# 03_-_MCU_and_Conn.net
KiCad netlist of a schematic drawn in Altium Designer
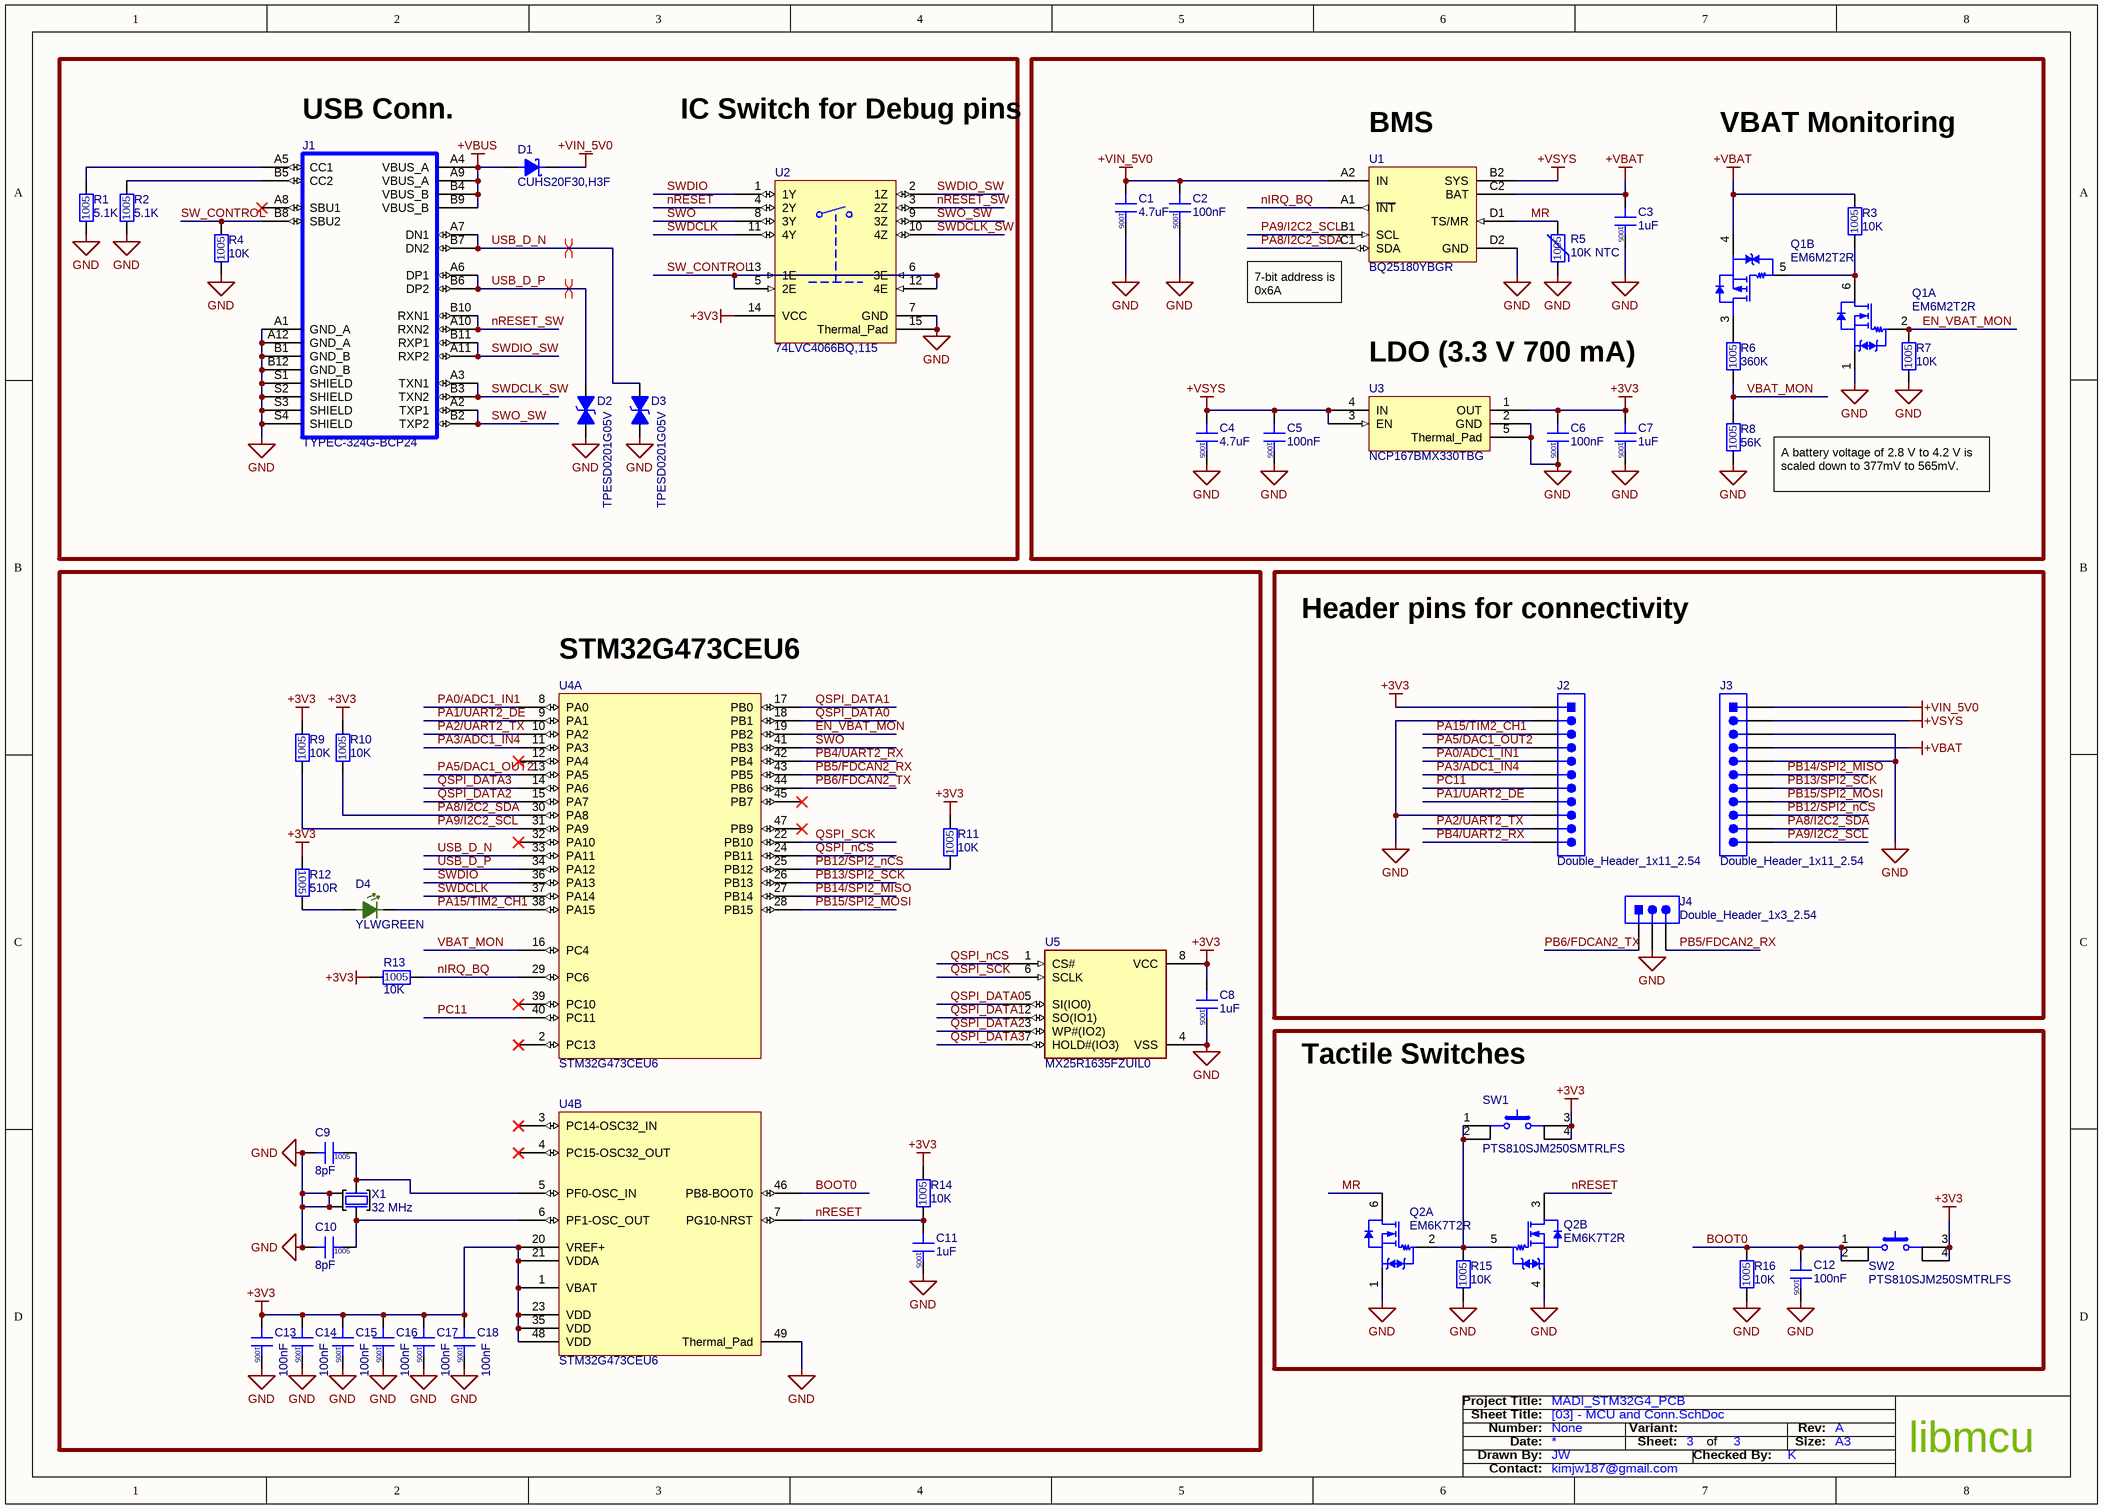
[diagram p0: [03] - MCU and Conn.SchDoc]

(export (version "E")
  (design (tool "Eeschema 10.0.6"))
  (components
    (comp (ref "C1")
      (value "4.7uF")
      (footprint "CAPC1005X06N")
      (description "CAP CER 4.7UF 10V X5R 0402")
      (fields
        (field (name "MANUFACTURER") "Samsung")
        (field (name "MANUFACTURER PART NUMBER") "CL05A475MP5NRNC")
      )
      (libsource (lib "Schlib-master") (part "CL05A475MP5NRNC"))
    )
    (comp (ref "C2")
      (value "100nF")
      (footprint "CAPC1005X06N")
      (description "CAP CER 0.1UF 50V X7R 0402")
      (fields
        (field (name "MANUFACTURER") "Murata")
        (field (name "MANUFACTURER PART NUMBER") "GRM155R71H104KE14D")
      )
      (libsource (lib "Schlib-master") (part "GRM155R71H104KE14D"))
    )
    (comp (ref "C3")
      (value "1uF")
      (footprint "CAPC1005X06N")
      (description "CAP CER 1UF 16V X5R 0402")
      (fields
        (field (name "MANUFACTURER") "Samsung")
        (field (name "MANUFACTURER PART NUMBER") "CL05A105KO5NNNC")
      )
      (libsource (lib "Schlib-master") (part "CL05A105KO5NNNC"))
    )
    (comp (ref "C4")
      (value "4.7uF")
      (footprint "CAPC1005X06N")
      (description "CAP CER 4.7UF 10V X5R 0402")
      (fields
        (field (name "MANUFACTURER") "Samsung")
        (field (name "MANUFACTURER PART NUMBER") "CL05A475MP5NRNC")
      )
      (libsource (lib "Schlib-master") (part "CL05A475MP5NRNC"))
    )
    (comp (ref "C5")
      (value "100nF")
      (footprint "CAPC1005X06N")
      (description "CAP CER 0.1UF 50V X7R 0402")
      (fields
        (field (name "MANUFACTURER") "Murata")
        (field (name "MANUFACTURER PART NUMBER") "GRM155R71H104KE14D")
      )
      (libsource (lib "Schlib-master") (part "GRM155R71H104KE14D"))
    )
    (comp (ref "C6")
      (value "100nF")
      (footprint "CAPC1005X06N")
      (description "CAP CER 0.1UF 50V X7R 0402")
      (fields
        (field (name "MANUFACTURER") "Murata")
        (field (name "MANUFACTURER PART NUMBER") "GRM155R71H104KE14D")
      )
      (libsource (lib "Schlib-master") (part "GRM155R71H104KE14D"))
    )
    (comp (ref "C7")
      (value "1uF")
      (footprint "CAPC1005X06N")
      (description "CAP CER 1UF 16V X5R 0402")
      (fields
        (field (name "MANUFACTURER") "Samsung")
        (field (name "MANUFACTURER PART NUMBER") "CL05A105KO5NNNC")
      )
      (libsource (lib "Schlib-master") (part "CL05A105KO5NNNC"))
    )
    (comp (ref "C8")
      (value "1uF")
      (footprint "CAPC1005X06N")
      (description "CAP CER 1UF 16V X5R 0402")
      (fields
        (field (name "MANUFACTURER") "Samsung")
        (field (name "MANUFACTURER PART NUMBER") "CL05A105KO5NNNC")
      )
      (libsource (lib "Schlib-master") (part "CL05A105KO5NNNC"))
    )
    (comp (ref "C9")
      (value "8pF")
      (footprint "CAPC1005X06N")
      (description "CAP CER 8PF 50V C0G/NP0 0402")
      (fields
        (field (name "MANUFACTURER") "Murata")
        (field (name "MANUFACTURER PART NUMBER") "GRM1555C1H8R0DA01D")
      )
      (libsource (lib "Schlib-master") (part "GRM1555C1H8R0DA01D"))
    )
    (comp (ref "C10")
      (value "8pF")
      (footprint "CAPC1005X06N")
      (description "CAP CER 8PF 50V C0G/NP0 0402")
      (fields
        (field (name "MANUFACTURER") "Murata")
        (field (name "MANUFACTURER PART NUMBER") "GRM1555C1H8R0DA01D")
      )
      (libsource (lib "Schlib-master") (part "GRM1555C1H8R0DA01D"))
    )
    (comp (ref "C11")
      (value "1uF")
      (footprint "CAPC1005X06N")
      (description "CAP CER 1UF 16V X5R 0402")
      (fields
        (field (name "MANUFACTURER") "Samsung")
        (field (name "MANUFACTURER PART NUMBER") "CL05A105KO5NNNC")
      )
      (libsource (lib "Schlib-master") (part "CL05A105KO5NNNC"))
    )
    (comp (ref "C12")
      (value "100nF")
      (footprint "CAPC1005X06N")
      (description "CAP CER 0.1UF 50V X7R 0402")
      (fields
        (field (name "MANUFACTURER") "Murata")
        (field (name "MANUFACTURER PART NUMBER") "GRM155R71H104KE14D")
      )
      (libsource (lib "Schlib-master") (part "GRM155R71H104KE14D"))
    )
    (comp (ref "C13")
      (value "100nF")
      (footprint "CAPC1005X06N")
      (description "CAP CER 0.1UF 50V X7R 0402")
      (fields
        (field (name "MANUFACTURER") "Murata")
        (field (name "MANUFACTURER PART NUMBER") "GRM155R71H104KE14D")
      )
      (libsource (lib "Schlib-master") (part "GRM155R71H104KE14D"))
    )
    (comp (ref "C14")
      (value "100nF")
      (footprint "CAPC1005X06N")
      (description "CAP CER 0.1UF 50V X7R 0402")
      (fields
        (field (name "MANUFACTURER") "Murata")
        (field (name "MANUFACTURER PART NUMBER") "GRM155R71H104KE14D")
      )
      (libsource (lib "Schlib-master") (part "GRM155R71H104KE14D"))
    )
    (comp (ref "C15")
      (value "100nF")
      (footprint "CAPC1005X06N")
      (description "CAP CER 0.1UF 50V X7R 0402")
      (fields
        (field (name "MANUFACTURER") "Murata")
        (field (name "MANUFACTURER PART NUMBER") "GRM155R71H104KE14D")
      )
      (libsource (lib "Schlib-master") (part "GRM155R71H104KE14D"))
    )
    (comp (ref "C16")
      (value "100nF")
      (footprint "CAPC1005X06N")
      (description "CAP CER 0.1UF 50V X7R 0402")
      (fields
        (field (name "MANUFACTURER") "Murata")
        (field (name "MANUFACTURER PART NUMBER") "GRM155R71H104KE14D")
      )
      (libsource (lib "Schlib-master") (part "GRM155R71H104KE14D"))
    )
    (comp (ref "C17")
      (value "100nF")
      (footprint "CAPC1005X06N")
      (description "CAP CER 0.1UF 50V X7R 0402")
      (fields
        (field (name "MANUFACTURER") "Murata")
        (field (name "MANUFACTURER PART NUMBER") "GRM155R71H104KE14D")
      )
      (libsource (lib "Schlib-master") (part "GRM155R71H104KE14D"))
    )
    (comp (ref "C18")
      (value "100nF")
      (footprint "CAPC1005X06N")
      (description "CAP CER 0.1UF 50V X7R 0402")
      (fields
        (field (name "MANUFACTURER") "Murata")
        (field (name "MANUFACTURER PART NUMBER") "GRM155R71H104KE14D")
      )
      (libsource (lib "Schlib-master") (part "GRM155R71H104KE14D"))
    )
    (comp (ref "D1")
      (value "CUHS20F30,H3F")
      (footprint "US2H-DIODE")
      (description "DIODE SCHOTTKY 30V 2A US2H")
      (fields (field (name "MANUFACTURER") "Toshiba"))
      (libsource (lib "Schlib-master") (part "CUHS20F30,H3F"))
    )
    (comp (ref "D2")
      (value "TPESD0201G05V")
      (footprint "DIOC0603X03N")
      (description "TVS DIODE 5.5VWM 40VC 0201")
      (fields (field (name "MANUFACTURER") "TECH PUBLIC"))
      (libsource (lib "Schlib-master") (part "TPESD0201G05V"))
    )
    (comp (ref "D3")
      (value "TPESD0201G05V")
      (footprint "DIOC0603X03N")
      (description "TVS DIODE 5.5VWM 40VC 0201")
      (fields (field (name "MANUFACTURER") "TECH PUBLIC"))
      (libsource (lib "Schlib-master") (part "TPESD0201G05V"))
    )
    (comp (ref "D4")
      (value "YLWGREEN")
      (footprint "LDIOC1608X08N")
      (description "LED YLW/GREEN DIFFUSED 1608 SMD")
      (fields
        (field (name "MANUFACTURER") "Everlight")
        (field (name "MANUFACTURER PART NUMBER") "19-217/G7C-AN1P2/3T")
      )
      (libsource (lib "Schlib-master") (part "19-217/G7C-AN1P2/3T"))
    )
    (comp (ref "J1")
      (value "TYPEC-324G-BCP24")
      (footprint "KUSBX-SMT3-CS-BTR_KYC")
      (description "CONN RCPT USB TYPE C, SMT PINS, TH SHIELD")
      (fields (field (name "MANUFACTURER") "XUNPU"))
      (libsource (lib "Schlib-master") (part "TYPEC-324G-BCP24"))
    )
    (comp (ref "J2")
      (value "Double_Header_1x11_2.54")
      (footprint "1x11_DOUBLE_HEADER_2.54")
      (libsource (lib "Schlib-master") (part "Double_Header_1x11_2.54"))
    )
    (comp (ref "J3")
      (value "Double_Header_1x11_2.54")
      (footprint "1x11_DOUBLE_HEADER_2.54")
      (libsource (lib "") (part "Double_Header_1x11_2.54_1"))
    )
    (comp (ref "J4")
      (value "Double_Header_1x3_2.54")
      (footprint "1x3_DOUBLE_HEADER_2.54")
      (libsource (lib "Schlib-master") (part "Double_Header_1x3_2.54"))
    )
    (comp (ref "Q1")
      (value "EM6M2T2R")
      (footprint "SOTFL50P160X55-6N")
      (description "MOSFET N/P-CH 20V 0.2A EMT6")
      (fields (field (name "MANUFACTURER") "Rohm"))
      (libsource (lib "Schlib-master") (part "EM6M2T2R"))
    )
    (comp (ref "Q2")
      (value "EM6K7T2R")
      (footprint "SOTFL50P160X55-6N")
      (description "MOSFET 2N-CH 20V 0.2A EMT6")
      (fields (field (name "MANUFACTURER") "Rohm"))
      (libsource (lib "Schlib-master") (part "EM6K7T2R"))
    )
    (comp (ref "R1")
      (value "5.1K")
      (footprint "RESC1005X04N")
      (description "RES SMD 5.1K OHM 1% 1/16W 0402")
      (fields
        (field (name "MANUFACTURER") "Yageo")
        (field (name "MANUFACTURER PART NUMBER") "RC0402FR-075K1L")
      )
      (libsource (lib "Schlib-master") (part "RC0402FR-075K1L"))
    )
    (comp (ref "R2")
      (value "5.1K")
      (footprint "RESC1005X04N")
      (description "RES SMD 5.1K OHM 1% 1/16W 0402")
      (fields
        (field (name "MANUFACTURER") "Yageo")
        (field (name "MANUFACTURER PART NUMBER") "RC0402FR-075K1L")
      )
      (libsource (lib "Schlib-master") (part "RC0402FR-075K1L"))
    )
    (comp (ref "R3")
      (value "10K")
      (footprint "RESC1005X04N")
      (description "RES SMD 10K OHM 1% 1/16W 0402")
      (fields
        (field (name "MANUFACTURER") "Yageo")
        (field (name "MANUFACTURER PART NUMBER") "RC0402FR-0710KL")
      )
      (libsource (lib "Schlib-master") (part "RC0402FR-0710KL"))
    )
    (comp (ref "R4")
      (value "10K")
      (footprint "RESC1005X04N")
      (description "RES SMD 10K OHM 1% 1/16W 0402")
      (fields
        (field (name "MANUFACTURER") "Yageo")
        (field (name "MANUFACTURER PART NUMBER") "RC0402FR-0710KL")
      )
      (libsource (lib "Schlib-master") (part "RC0402FR-0710KL"))
    )
    (comp (ref "R5")
      (value "10K NTC")
      (footprint "NTC1005X05N")
      (description "THERMISTOR NTC 10KOHM 3380K 0402")
      (fields
        (field (name "MANUFACTURER") "Murata")
        (field (name "MANUFACTURER PART NUMBER") "NCP15XH103F03RC")
      )
      (libsource (lib "Schlib-master") (part "NCP15XH103F03RC"))
    )
    (comp (ref "R6")
      (value "360K")
      (footprint "RESC1005X04N")
      (description "RES SMD 360K OHM 1% 1/16W 0402")
      (fields
        (field (name "MANUFACTURER") "Yageo")
        (field (name "MANUFACTURER PART NUMBER") "RC0402FR-07360KL")
      )
      (libsource (lib "Schlib-master") (part "RC0402FR-07360KL"))
    )
    (comp (ref "R7")
      (value "10K")
      (footprint "RESC1005X04N")
      (description "RES SMD 10K OHM 1% 1/16W 0402")
      (fields
        (field (name "MANUFACTURER") "Yageo")
        (field (name "MANUFACTURER PART NUMBER") "RC0402FR-0710KL")
      )
      (libsource (lib "Schlib-master") (part "RC0402FR-0710KL"))
    )
    (comp (ref "R8")
      (value "56K")
      (footprint "RESC1005X04N")
      (description "RES SMD 56K OHM 1% 1/16W 0402")
      (fields
        (field (name "MANUFACTURER") "Yageo")
        (field (name "MANUFACTURER PART NUMBER") "RC0402FR-0756KL")
      )
      (libsource (lib "Schlib-master") (part "RC0402FR-0756KL"))
    )
    (comp (ref "R9")
      (value "10K")
      (footprint "RESC1005X04N")
      (description "RES SMD 10K OHM 1% 1/16W 0402")
      (fields
        (field (name "MANUFACTURER") "Yageo")
        (field (name "MANUFACTURER PART NUMBER") "RC0402FR-0710KL")
      )
      (libsource (lib "Schlib-master") (part "RC0402FR-0710KL"))
    )
    (comp (ref "R10")
      (value "10K")
      (footprint "RESC1005X04N")
      (description "RES SMD 10K OHM 1% 1/16W 0402")
      (fields
        (field (name "MANUFACTURER") "Yageo")
        (field (name "MANUFACTURER PART NUMBER") "RC0402FR-0710KL")
      )
      (libsource (lib "Schlib-master") (part "RC0402FR-0710KL"))
    )
    (comp (ref "R11")
      (value "10K")
      (footprint "RESC1005X04N")
      (description "RES SMD 10K OHM 1% 1/16W 0402")
      (fields
        (field (name "MANUFACTURER") "Yageo")
        (field (name "MANUFACTURER PART NUMBER") "RC0402FR-0710KL")
      )
      (libsource (lib "Schlib-master") (part "RC0402FR-0710KL"))
    )
    (comp (ref "R12")
      (value "510R")
      (footprint "RESC1005X04N")
      (description "RES SMD 510 OHM 1% 1/16W 0402")
      (fields (field (name "TOLERANCE") "1%") (field (name "MANUFACTURER") "Yageo"))
      (libsource (lib "Schlib-master") (part "RC0402FR-07510RL"))
    )
    (comp (ref "R13")
      (value "10K")
      (footprint "RESC1005X04N")
      (description "RES SMD 10K OHM 1% 1/16W 0402")
      (fields
        (field (name "MANUFACTURER") "Yageo")
        (field (name "MANUFACTURER PART NUMBER") "RC0402FR-0710KL")
      )
      (libsource (lib "") (part "RC0402FR-0710KL_1"))
    )
    (comp (ref "R14")
      (value "10K")
      (footprint "RESC1005X04N")
      (description "RES SMD 10K OHM 1% 1/16W 0402")
      (fields
        (field (name "MANUFACTURER") "Yageo")
        (field (name "MANUFACTURER PART NUMBER") "RC0402FR-0710KL")
      )
      (libsource (lib "Schlib-master") (part "RC0402FR-0710KL"))
    )
    (comp (ref "R15")
      (value "10K")
      (footprint "RESC1005X04N")
      (description "RES SMD 10K OHM 1% 1/16W 0402")
      (fields
        (field (name "MANUFACTURER") "Yageo")
        (field (name "MANUFACTURER PART NUMBER") "RC0402FR-0710KL")
      )
      (libsource (lib "Schlib-master") (part "RC0402FR-0710KL"))
    )
    (comp (ref "R16")
      (value "10K")
      (footprint "RESC1005X04N")
      (description "RES SMD 10K OHM 1% 1/16W 0402")
      (fields
        (field (name "MANUFACTURER") "Yageo")
        (field (name "MANUFACTURER PART NUMBER") "RC0402FR-0710KL")
      )
      (libsource (lib "Schlib-master") (part "RC0402FR-0710KL"))
    )
    (comp (ref "SW1")
      (value "PTS810SJM250SMTRLFS")
      (footprint "PTS810")
      (description "SWITCH TACTILE SPST-NO 0.05A 16V")
      (fields (field (name "MANUFACTURER") "ITT C&K"))
      (libsource (lib "Schlib-master") (part "PTS810SJM250SMTRLFS"))
    )
    (comp (ref "SW2")
      (value "PTS810SJM250SMTRLFS")
      (footprint "PTS810")
      (description "SWITCH TACTILE SPST-NO 0.05A 16V")
      (fields (field (name "MANUFACTURER") "ITT C&K"))
      (libsource (lib "Schlib-master") (part "PTS810SJM250SMTRLFS"))
    )
    (comp (ref "U1")
      (value "BQ25180YBGR")
      (footprint "BGA8C40P2X4_100X155X50_YBG0008")
      (description "IC 1-A LI-ION IC PROGRAMMABLE CHARG")
      (fields (field (name "MANUFACTURER") "Texas Instruments"))
      (libsource (lib "Schlib-master") (part "BQ25180YBGR"))
    )
    (comp (ref "U2")
      (value "74LVC4066BQ,115")
      (footprint "QFN50P250X300X100_HS-15N")
      (description "IC SWITCH QUAD SPST 14DHVQFN")
      (fields (field (name "MANUFACTURER") "Nexperia"))
      (libsource (lib "Schlib-master") (part "74LVC4066BQ,115"))
    )
    (comp (ref "U3")
      (value "NCP167BMX330TBG")
      (footprint "NCP167")
      (description "IC REG LINEAR 3.3V 700MA 4XDFN")
      (fields (field (name "MANUFACTURER") "ON Semiconductor"))
      (libsource (lib "Schlib-master") (part "NCP167BMX330TBG"))
    )
    (comp (ref "U4")
      (value "STM32G473CEU6")
      (footprint "QFN50P700X700X60_HS-49N")
      (description "IC MCU 32BIT 512KB FLSH 48UFQFPN")
      (fields (field (name "MANUFACTURER") "STMicroelectronics"))
      (libsource (lib "Schlib-master") (part "STM32G473CEU6"))
    )
    (comp (ref "U5")
      (value "MX25R1635FZUIL0")
      (footprint "USON8_3X2")
      (description "IC FLASH 16MBIT SPI/QUAD 8USON")
      (fields (field (name "MANUFACTURER") "Macronix"))
      (libsource (lib "Schlib-master") (part "MX25R1635FZUIL0"))
    )
    (comp (ref "X1")
      (value "32 MHz")
      (footprint "XT2016_ECS")
      (description "CRYSTAL 32.0000MHZ 8PF SMD")
      (fields
        (field (name "MANUFACTURER") "Seiko")
        (field (name "MANUFACTURER PART NUMBER") "Q22FA1280002500")
      )
      (libsource (lib "Schlib-master") (part "Q22FA1280002500"))
    )
  )
  (nets
    (net (code "1") (name "+3V3") (class "Default")
      (node (ref "C13") (pin "2") (pinfunction "2_2") (pintype "passive"))
      (node (ref "C14") (pin "2") (pinfunction "2_2") (pintype "passive"))
      (node (ref "C15") (pin "2") (pinfunction "2_2") (pintype "passive"))
      (node (ref "C16") (pin "2") (pinfunction "2_2") (pintype "passive"))
      (node (ref "C17") (pin "2") (pinfunction "2_2") (pintype "passive"))
      (node (ref "C18") (pin "2") (pinfunction "2_2") (pintype "passive"))
      (node (ref "C6") (pin "2") (pinfunction "2_2") (pintype "passive"))
      (node (ref "C7") (pin "2") (pinfunction "2_2") (pintype "passive"))
      (node (ref "C8") (pin "2") (pinfunction "2_2") (pintype "passive"))
      (node (ref "J2") (pin "1") (pinfunction "1_1") (pintype "passive"))
      (node (ref "R10") (pin "2") (pinfunction "2_2") (pintype "passive"))
      (node (ref "R11") (pin "2") (pinfunction "2_2") (pintype "passive"))
      (node (ref "R12") (pin "2") (pinfunction "2_2") (pintype "passive"))
      (node (ref "R13") (pin "1") (pinfunction "1_1") (pintype "passive"))
      (node (ref "R14") (pin "2") (pinfunction "2_2") (pintype "passive"))
      (node (ref "R9") (pin "2") (pinfunction "2_2") (pintype "passive"))
      (node (ref "SW1") (pin "3") (pinfunction "2_3") (pintype "passive"))
      (node (ref "SW1") (pin "4") (pinfunction "1_4") (pintype "passive"))
      (node (ref "SW2") (pin "3") (pinfunction "2_3") (pintype "passive"))
      (node (ref "SW2") (pin "4") (pinfunction "1_4") (pintype "passive"))
      (node (ref "U2") (pin "14") (pinfunction "VCC_14") (pintype "power_in"))
      (node (ref "U3") (pin "1") (pinfunction "OUT_1") (pintype "power_in"))
      (node (ref "U4") (pin "1") (pinfunction "VBAT_1") (pintype "power_in"))
      (node (ref "U4") (pin "20") (pinfunction "VREF+_20") (pintype "power_in"))
      (node (ref "U4") (pin "21") (pinfunction "VDDA_21") (pintype "power_in"))
      (node (ref "U4") (pin "23") (pinfunction "VDD_23") (pintype "power_in"))
      (node (ref "U4") (pin "35") (pinfunction "VDD_35") (pintype "power_in"))
      (node (ref "U4") (pin "48") (pinfunction "VDD_48") (pintype "power_in"))
      (node (ref "U5") (pin "8") (pinfunction "VCC_8") (pintype "power_in"))
    )
    (net (code "2") (name "+VBAT") (class "Default")
      (node (ref "C3") (pin "2") (pinfunction "2_2") (pintype "passive"))
      (node (ref "J3") (pin "4") (pinfunction "4_4") (pintype "passive"))
      (node (ref "Q1") (pin "4") (pinfunction "S_4") (pintype "passive"))
      (node (ref "R3") (pin "2") (pinfunction "2_2") (pintype "passive"))
      (node (ref "U1") (pin "C2") (pinfunction "BAT_C2") (pintype "power_in"))
    )
    (net (code "3") (name "+VBUS") (class "Default")
      (node (ref "D1") (pin "2") (pinfunction "Anode_2") (pintype "passive"))
      (node (ref "J1") (pin "A4") (pinfunction "VBUS_A_A4") (pintype "power_in"))
      (node (ref "J1") (pin "A9") (pinfunction "VBUS_A_A9") (pintype "power_in"))
      (node (ref "J1") (pin "B4") (pinfunction "VBUS_B_B4") (pintype "power_in"))
      (node (ref "J1") (pin "B9") (pinfunction "VBUS_B_B9") (pintype "power_in"))
    )
    (net (code "4") (name "+VIN_5V0") (class "Default")
      (node (ref "C1") (pin "2") (pinfunction "2_2") (pintype "passive"))
      (node (ref "C2") (pin "2") (pinfunction "2_2") (pintype "passive"))
      (node (ref "D1") (pin "1") (pinfunction "Cathode_1") (pintype "passive"))
      (node (ref "J3") (pin "1") (pinfunction "1_1") (pintype "passive"))
      (node (ref "U1") (pin "A2") (pinfunction "IN_A2") (pintype "power_in"))
    )
    (net (code "5") (name "+VSYS") (class "Default")
      (node (ref "C4") (pin "2") (pinfunction "2_2") (pintype "passive"))
      (node (ref "C5") (pin "2") (pinfunction "2_2") (pintype "passive"))
      (node (ref "J3") (pin "2") (pinfunction "2_2") (pintype "passive"))
      (node (ref "U1") (pin "B2") (pinfunction "SYS_B2") (pintype "power_in"))
      (node (ref "U3") (pin "3") (pinfunction "EN_3") (pintype "input"))
      (node (ref "U3") (pin "4") (pinfunction "IN_4") (pintype "power_in"))
    )
    (net (code "6") (name "/BOOT0") (class "Default")
      (node (ref "C12") (pin "2") (pinfunction "2_2") (pintype "passive"))
      (node (ref "R16") (pin "2") (pinfunction "2_2") (pintype "passive"))
      (node (ref "SW2") (pin "1") (pinfunction "1_1") (pintype "passive"))
      (node (ref "SW2") (pin "2") (pinfunction "2_2") (pintype "passive"))
      (node (ref "U4") (pin "46") (pinfunction "PB8-BOOT0_46") (pintype "bidirectional"))
    )
    (net (code "7") (name "/EN_VBAT_MON") (class "Default")
      (node (ref "Q1") (pin "2") (pinfunction "G_2") (pintype "passive"))
      (node (ref "R7") (pin "2") (pinfunction "2_2") (pintype "passive"))
      (node (ref "U4") (pin "19") (pinfunction "PB2_19") (pintype "bidirectional"))
    )
    (net (code "8") (name "/MR") (class "Default")
      (node (ref "Q2") (pin "6") (pinfunction "D_6") (pintype "passive"))
      (node (ref "R5") (pin "2") (pinfunction "2_2") (pintype "passive"))
      (node (ref "U1") (pin "D1") (pinfunction "TS/MR_D1") (pintype "input"))
    )
    (net (code "9") (name "/PA0{slash}ADC1_IN1") (class "Default")
      (node (ref "J2") (pin "5") (pinfunction "5_5") (pintype "passive"))
      (node (ref "U4") (pin "8") (pinfunction "PA0_8") (pintype "bidirectional"))
    )
    (net (code "10") (name "/PA1{slash}UART2_DE") (class "Default")
      (node (ref "J2") (pin "8") (pinfunction "8_8") (pintype "passive"))
      (node (ref "U4") (pin "9") (pinfunction "PA1_9") (pintype "bidirectional"))
    )
    (net (code "11") (name "/PA2{slash}UART2_TX") (class "Default")
      (node (ref "J2") (pin "10") (pinfunction "10_10") (pintype "passive"))
      (node (ref "U4") (pin "10") (pinfunction "PA2_10") (pintype "bidirectional"))
    )
    (net (code "12") (name "/PA3{slash}ADC1_IN4") (class "Default")
      (node (ref "J2") (pin "6") (pinfunction "6_6") (pintype "passive"))
      (node (ref "U4") (pin "11") (pinfunction "PA3_11") (pintype "bidirectional"))
    )
    (net (code "13") (name "/PA5{slash}DAC1_OUT2") (class "Default")
      (node (ref "J2") (pin "4") (pinfunction "4_4") (pintype "passive"))
      (node (ref "U4") (pin "13") (pinfunction "PA5_13") (pintype "bidirectional"))
    )
    (net (code "14") (name "/PA8{slash}I2C2_SDA") (class "Default")
      (node (ref "J3") (pin "10") (pinfunction "10_10") (pintype "passive"))
      (node (ref "R10") (pin "1") (pinfunction "1_1") (pintype "passive"))
      (node (ref "U1") (pin "C1") (pinfunction "SDA_C1") (pintype "bidirectional"))
      (node (ref "U4") (pin "30") (pinfunction "PA8_30") (pintype "bidirectional"))
    )
    (net (code "15") (name "/PA9{slash}I2C2_SCL") (class "Default")
      (node (ref "J3") (pin "11") (pinfunction "11_11") (pintype "passive"))
      (node (ref "R9") (pin "1") (pinfunction "1_1") (pintype "passive"))
      (node (ref "U1") (pin "B1") (pinfunction "SCL_B1") (pintype "input"))
      (node (ref "U4") (pin "31") (pinfunction "PA9_31") (pintype "bidirectional"))
    )
    (net (code "16") (name "/PA15{slash}TIM2_CH1") (class "Default")
      (node (ref "D4") (pin "K") (pinfunction "2_K") (pintype "passive"))
      (node (ref "J2") (pin "3") (pinfunction "3_3") (pintype "passive"))
      (node (ref "U4") (pin "38") (pinfunction "PA15_38") (pintype "bidirectional"))
    )
    (net (code "17") (name "/PB4{slash}UART2_RX") (class "Default")
      (node (ref "J2") (pin "11") (pinfunction "11_11") (pintype "passive"))
      (node (ref "U4") (pin "42") (pinfunction "PB4_42") (pintype "bidirectional"))
    )
    (net (code "18") (name "/PB5{slash}FDCAN2_RX") (class "Default")
      (node (ref "J4") (pin "3") (pinfunction "3_3") (pintype "passive"))
      (node (ref "U4") (pin "43") (pinfunction "PB5_43") (pintype "bidirectional"))
    )
    (net (code "19") (name "/PB6{slash}FDCAN2_TX") (class "Default")
      (node (ref "J4") (pin "1") (pinfunction "1_1") (pintype "passive"))
      (node (ref "U4") (pin "44") (pinfunction "PB6_44") (pintype "bidirectional"))
    )
    (net (code "20") (name "/PB12{slash}SPI2_nCS") (class "Default")
      (node (ref "J3") (pin "9") (pinfunction "9_9") (pintype "passive"))
      (node (ref "R11") (pin "1") (pinfunction "1_1") (pintype "passive"))
      (node (ref "U4") (pin "25") (pinfunction "PB12_25") (pintype "bidirectional"))
    )
    (net (code "21") (name "/PB13{slash}SPI2_SCK") (class "Default")
      (node (ref "J3") (pin "7") (pinfunction "7_7") (pintype "passive"))
      (node (ref "U4") (pin "26") (pinfunction "PB13_26") (pintype "bidirectional"))
    )
    (net (code "22") (name "/PB14{slash}SPI2_MISO") (class "Default")
      (node (ref "J3") (pin "6") (pinfunction "6_6") (pintype "passive"))
      (node (ref "U4") (pin "27") (pinfunction "PB14_27") (pintype "bidirectional"))
    )
    (net (code "23") (name "/PB15{slash}SPI2_MOSI") (class "Default")
      (node (ref "J3") (pin "8") (pinfunction "8_8") (pintype "passive"))
      (node (ref "U4") (pin "28") (pinfunction "PB15_28") (pintype "bidirectional"))
    )
    (net (code "24") (name "/PC11") (class "Default")
      (node (ref "J2") (pin "7") (pinfunction "7_7") (pintype "passive"))
      (node (ref "U4") (pin "40") (pinfunction "PC11_40") (pintype "bidirectional"))
    )
    (net (code "25") (name "/QSPI_DATA0") (class "Default")
      (node (ref "U4") (pin "18") (pinfunction "PB1_18") (pintype "bidirectional"))
      (node (ref "U5") (pin "5") (pinfunction "SI(IO0)_5") (pintype "bidirectional"))
    )
    (net (code "26") (name "/QSPI_DATA1") (class "Default")
      (node (ref "U4") (pin "17") (pinfunction "PB0_17") (pintype "bidirectional"))
      (node (ref "U5") (pin "2") (pinfunction "SO(IO1)_2") (pintype "bidirectional"))
    )
    (net (code "27") (name "/QSPI_DATA2") (class "Default")
      (node (ref "U4") (pin "15") (pinfunction "PA7_15") (pintype "bidirectional"))
      (node (ref "U5") (pin "3") (pinfunction "WP#(IO2)_3") (pintype "bidirectional"))
    )
    (net (code "28") (name "/QSPI_DATA3") (class "Default")
      (node (ref "U4") (pin "14") (pinfunction "PA6_14") (pintype "bidirectional"))
      (node (ref "U5") (pin "7") (pinfunction "HOLD#(IO3)_7") (pintype "bidirectional"))
    )
    (net (code "29") (name "/QSPI_SCK") (class "Default")
      (node (ref "U4") (pin "22") (pinfunction "PB10_22") (pintype "bidirectional"))
      (node (ref "U5") (pin "6") (pinfunction "SCLK_6") (pintype "input"))
    )
    (net (code "30") (name "/QSPI_nCS") (class "Default")
      (node (ref "U4") (pin "24") (pinfunction "PB11_24") (pintype "bidirectional"))
      (node (ref "U5") (pin "1") (pinfunction "CS#_1") (pintype "input"))
    )
    (net (code "31") (name "/SWDCLK") (class "Default")
      (node (ref "U2") (pin "11") (pinfunction "4Y_11") (pintype "bidirectional"))
      (node (ref "U4") (pin "37") (pinfunction "PA14_37") (pintype "bidirectional"))
    )
    (net (code "32") (name "/SWDCLK_SW") (class "Default")
      (node (ref "J1") (pin "A3") (pinfunction "TXN1_A3") (pintype "bidirectional"))
      (node (ref "J1") (pin "B3") (pinfunction "TXN2_B3") (pintype "bidirectional"))
      (node (ref "U2") (pin "10") (pinfunction "4Z_10") (pintype "bidirectional"))
    )
    (net (code "33") (name "/SWDIO") (class "Default")
      (node (ref "U2") (pin "1") (pinfunction "1Y_1") (pintype "bidirectional"))
      (node (ref "U4") (pin "36") (pinfunction "PA13_36") (pintype "bidirectional"))
    )
    (net (code "34") (name "/SWDIO_SW") (class "Default")
      (node (ref "J1") (pin "A11") (pinfunction "RXP2_A11") (pintype "bidirectional"))
      (node (ref "J1") (pin "B11") (pinfunction "RXP1_B11") (pintype "bidirectional"))
      (node (ref "U2") (pin "2") (pinfunction "1Z_2") (pintype "bidirectional"))
    )
    (net (code "35") (name "/SWO") (class "Default")
      (node (ref "U2") (pin "8") (pinfunction "3Y_8") (pintype "bidirectional"))
      (node (ref "U4") (pin "41") (pinfunction "PB3_41") (pintype "bidirectional"))
    )
    (net (code "36") (name "/SWO_SW") (class "Default")
      (node (ref "J1") (pin "A2") (pinfunction "TXP1_A2") (pintype "bidirectional"))
      (node (ref "J1") (pin "B2") (pinfunction "TXP2_B2") (pintype "bidirectional"))
      (node (ref "U2") (pin "9") (pinfunction "3Z_9") (pintype "bidirectional"))
    )
    (net (code "37") (name "/SW_CONTROL") (class "Default")
      (node (ref "J1") (pin "B8") (pinfunction "SBU2_B8") (pintype "bidirectional"))
      (node (ref "R4") (pin "2") (pinfunction "2_2") (pintype "passive"))
      (node (ref "U2") (pin "12") (pinfunction "4E_12") (pintype "input"))
      (node (ref "U2") (pin "13") (pinfunction "1E_13") (pintype "input"))
      (node (ref "U2") (pin "5") (pinfunction "2E_5") (pintype "input"))
      (node (ref "U2") (pin "6") (pinfunction "3E_6") (pintype "input"))
    )
    (net (code "38") (name "/USB_D_N") (class "Default")
      (node (ref "D3") (pin "1") (pinfunction "1_1") (pintype "passive"))
      (node (ref "J1") (pin "A7") (pinfunction "DN1_A7") (pintype "bidirectional"))
      (node (ref "J1") (pin "B7") (pinfunction "DN2_B7") (pintype "bidirectional"))
      (node (ref "U4") (pin "33") (pinfunction "PA11_33") (pintype "bidirectional"))
    )
    (net (code "39") (name "/USB_D_P") (class "Default")
      (node (ref "D2") (pin "1") (pinfunction "1_1") (pintype "passive"))
      (node (ref "J1") (pin "A6") (pinfunction "DP1_A6") (pintype "bidirectional"))
      (node (ref "J1") (pin "B6") (pinfunction "DP2_B6") (pintype "bidirectional"))
      (node (ref "U4") (pin "34") (pinfunction "PA12_34") (pintype "bidirectional"))
    )
    (net (code "40") (name "/VBAT_MON") (class "Default")
      (node (ref "R6") (pin "1") (pinfunction "1_1") (pintype "passive"))
      (node (ref "R8") (pin "2") (pinfunction "2_2") (pintype "passive"))
      (node (ref "U4") (pin "16") (pinfunction "PC4_16") (pintype "bidirectional"))
    )
    (net (code "41") (name "/nIRQ_BQ") (class "Default")
      (node (ref "R13") (pin "2") (pinfunction "2_2") (pintype "passive"))
      (node (ref "U1") (pin "A1") (pinfunction "~{INT}_A1") (pintype "output"))
      (node (ref "U4") (pin "29") (pinfunction "PC6_29") (pintype "bidirectional"))
    )
    (net (code "42") (name "/nRESET") (class "Default")
      (node (ref "C11") (pin "2") (pinfunction "2_2") (pintype "passive"))
      (node (ref "Q2") (pin "3") (pinfunction "D_3") (pintype "passive"))
      (node (ref "R14") (pin "1") (pinfunction "1_1") (pintype "passive"))
      (node (ref "U2") (pin "4") (pinfunction "2Y_4") (pintype "bidirectional"))
      (node (ref "U4") (pin "7") (pinfunction "PG10-NRST_7") (pintype "bidirectional"))
    )
    (net (code "43") (name "/nRESET_SW") (class "Default")
      (node (ref "J1") (pin "A10") (pinfunction "RXN2_A10") (pintype "bidirectional"))
      (node (ref "J1") (pin "B10") (pinfunction "RXN1_B10") (pintype "bidirectional"))
      (node (ref "U2") (pin "3") (pinfunction "2Z_3") (pintype "bidirectional"))
    )
    (net (code "44") (name "GND") (class "Default")
      (node (ref "C1") (pin "1") (pinfunction "1_1") (pintype "passive"))
      (node (ref "C10") (pin "2") (pinfunction "2_2") (pintype "passive"))
      (node (ref "C11") (pin "1") (pinfunction "1_1") (pintype "passive"))
      (node (ref "C12") (pin "1") (pinfunction "1_1") (pintype "passive"))
      (node (ref "C13") (pin "1") (pinfunction "1_1") (pintype "passive"))
      (node (ref "C14") (pin "1") (pinfunction "1_1") (pintype "passive"))
      (node (ref "C15") (pin "1") (pinfunction "1_1") (pintype "passive"))
      (node (ref "C16") (pin "1") (pinfunction "1_1") (pintype "passive"))
      (node (ref "C17") (pin "1") (pinfunction "1_1") (pintype "passive"))
      (node (ref "C18") (pin "1") (pinfunction "1_1") (pintype "passive"))
      (node (ref "C2") (pin "1") (pinfunction "1_1") (pintype "passive"))
      (node (ref "C3") (pin "1") (pinfunction "1_1") (pintype "passive"))
      (node (ref "C4") (pin "1") (pinfunction "1_1") (pintype "passive"))
      (node (ref "C5") (pin "1") (pinfunction "1_1") (pintype "passive"))
      (node (ref "C6") (pin "1") (pinfunction "1_1") (pintype "passive"))
      (node (ref "C7") (pin "1") (pinfunction "1_1") (pintype "passive"))
      (node (ref "C8") (pin "1") (pinfunction "1_1") (pintype "passive"))
      (node (ref "C9") (pin "2") (pinfunction "2_2") (pintype "passive"))
      (node (ref "D2") (pin "2") (pinfunction "2_2") (pintype "passive"))
      (node (ref "D3") (pin "2") (pinfunction "2_2") (pintype "passive"))
      (node (ref "J1") (pin "A1") (pinfunction "GND_A_A1") (pintype "power_in"))
      (node (ref "J1") (pin "A12") (pinfunction "GND_A_A12") (pintype "power_in"))
      (node (ref "J1") (pin "B1") (pinfunction "GND_B_B1") (pintype "power_in"))
      (node (ref "J1") (pin "B12") (pinfunction "GND_B_B12") (pintype "power_in"))
      (node (ref "J1") (pin "S1") (pinfunction "SHIELD_S1") (pintype "passive"))
      (node (ref "J1") (pin "S2") (pinfunction "SHIELD_S2") (pintype "passive"))
      (node (ref "J1") (pin "S3") (pinfunction "SHIELD_S3") (pintype "passive"))
      (node (ref "J1") (pin "S4") (pinfunction "SHIELD_S4") (pintype "passive"))
      (node (ref "J2") (pin "2") (pinfunction "2_2") (pintype "passive"))
      (node (ref "J2") (pin "9") (pinfunction "9_9") (pintype "passive"))
      (node (ref "J3") (pin "3") (pinfunction "3_3") (pintype "passive"))
      (node (ref "J3") (pin "5") (pinfunction "5_5") (pintype "passive"))
      (node (ref "J4") (pin "2") (pinfunction "2_2") (pintype "passive"))
      (node (ref "Q1") (pin "1") (pinfunction "S_1") (pintype "passive"))
      (node (ref "Q2") (pin "1") (pinfunction "S_1") (pintype "passive"))
      (node (ref "Q2") (pin "4") (pinfunction "S_4") (pintype "passive"))
      (node (ref "R1") (pin "1") (pinfunction "1_1") (pintype "passive"))
      (node (ref "R15") (pin "1") (pinfunction "1_1") (pintype "passive"))
      (node (ref "R16") (pin "1") (pinfunction "1_1") (pintype "passive"))
      (node (ref "R2") (pin "1") (pinfunction "1_1") (pintype "passive"))
      (node (ref "R4") (pin "1") (pinfunction "1_1") (pintype "passive"))
      (node (ref "R5") (pin "1") (pinfunction "1_1") (pintype "passive"))
      (node (ref "R7") (pin "1") (pinfunction "1_1") (pintype "passive"))
      (node (ref "R8") (pin "1") (pinfunction "1_1") (pintype "passive"))
      (node (ref "U1") (pin "D2") (pinfunction "GND_D2") (pintype "power_in"))
      (node (ref "U2") (pin "15") (pinfunction "Thermal_Pad_15") (pintype "power_in"))
      (node (ref "U2") (pin "7") (pinfunction "GND_7") (pintype "power_in"))
      (node (ref "U3") (pin "2") (pinfunction "GND_2") (pintype "power_in"))
      (node (ref "U3") (pin "5") (pinfunction "Thermal_Pad_5") (pintype "passive"))
      (node (ref "U4") (pin "49") (pinfunction "Thermal_Pad_49") (pintype "power_in"))
      (node (ref "U5") (pin "4") (pinfunction "VSS_4") (pintype "power_in"))
      (node (ref "X1") (pin "2") (pinfunction "GND_2") (pintype "passive"))
      (node (ref "X1") (pin "4") (pinfunction "GND_4") (pintype "passive"))
    )
    (net (code "45") (name "Net-(D4-1)") (class "Default")
      (node (ref "D4") (pin "A") (pinfunction "1_A") (pintype "passive"))
      (node (ref "R12") (pin "1") (pinfunction "1_1") (pintype "passive"))
    )
    (net (code "46") (name "Net-(J1-CC1)") (class "Default")
      (node (ref "J1") (pin "A5") (pinfunction "CC1_A5") (pintype "bidirectional"))
      (node (ref "R1") (pin "2") (pinfunction "2_2") (pintype "passive"))
    )
    (net (code "47") (name "Net-(J1-CC2)") (class "Default")
      (node (ref "J1") (pin "B5") (pinfunction "CC2_B5") (pintype "bidirectional"))
      (node (ref "R2") (pin "2") (pinfunction "2_2") (pintype "passive"))
    )
    (net (code "48") (name "Net-(Q1A-D)") (class "Default")
      (node (ref "Q1") (pin "5") (pinfunction "G_5") (pintype "passive"))
      (node (ref "Q1") (pin "6") (pinfunction "D_6") (pintype "passive"))
      (node (ref "R3") (pin "1") (pinfunction "1_1") (pintype "passive"))
    )
    (net (code "49") (name "Net-(Q1B-D)") (class "Default")
      (node (ref "Q1") (pin "3") (pinfunction "D_3") (pintype "passive"))
      (node (ref "R6") (pin "2") (pinfunction "2_2") (pintype "passive"))
    )
    (net (code "50") (name "Net-(Q2A-G)") (class "Default")
      (node (ref "Q2") (pin "2") (pinfunction "G_2") (pintype "passive"))
      (node (ref "Q2") (pin "5") (pinfunction "G_5") (pintype "passive"))
      (node (ref "R15") (pin "2") (pinfunction "2_2") (pintype "passive"))
      (node (ref "SW1") (pin "1") (pinfunction "1_1") (pintype "passive"))
      (node (ref "SW1") (pin "2") (pinfunction "2_2") (pintype "passive"))
    )
    (net (code "51") (name "Net-(U4B-PF0-OSC_IN)") (class "Default")
      (node (ref "C9") (pin "1") (pinfunction "1_1") (pintype "passive"))
      (node (ref "U4") (pin "5") (pinfunction "PF0-OSC_IN_5") (pintype "bidirectional"))
      (node (ref "X1") (pin "1") (pinfunction "IN_1") (pintype "passive"))
    )
    (net (code "52") (name "Net-(U4B-PF1-OSC_OUT)") (class "Default")
      (node (ref "C10") (pin "1") (pinfunction "1_1") (pintype "passive"))
      (node (ref "U4") (pin "6") (pinfunction "PF1-OSC_OUT_6") (pintype "bidirectional"))
      (node (ref "X1") (pin "3") (pinfunction "OUT_3") (pintype "passive"))
    )
    (net (code "53") (name "unconnected-(J1-SBU1-PadA8)") (class "Default")
      (node (ref "J1") (pin "A8") (pinfunction "SBU1_A8") (pintype "bidirectional+no_connect"))
    )
    (net (code "54") (name "unconnected-(U4A-PA4-Pad12)") (class "Default")
      (node (ref "U4") (pin "12") (pinfunction "PA4_12") (pintype "bidirectional+no_connect"))
    )
    (net (code "55") (name "unconnected-(U4A-PA10-Pad32)") (class "Default")
      (node (ref "U4") (pin "32") (pinfunction "PA10_32") (pintype "bidirectional+no_connect"))
    )
    (net (code "56") (name "unconnected-(U4A-PB7-Pad45)") (class "Default")
      (node (ref "U4") (pin "45") (pinfunction "PB7_45") (pintype "bidirectional+no_connect"))
    )
    (net (code "57") (name "unconnected-(U4A-PB9-Pad47)") (class "Default")
      (node (ref "U4") (pin "47") (pinfunction "PB9_47") (pintype "bidirectional+no_connect"))
    )
    (net (code "58") (name "unconnected-(U4A-PC10-Pad39)") (class "Default")
      (node (ref "U4") (pin "39") (pinfunction "PC10_39") (pintype "bidirectional+no_connect"))
    )
    (net (code "59") (name "unconnected-(U4A-PC13-Pad2)") (class "Default")
      (node (ref "U4") (pin "2") (pinfunction "PC13_2") (pintype "bidirectional+no_connect"))
    )
    (net (code "60") (name "unconnected-(U4B-PC14-OSC32_IN-Pad3)") (class "Default")
      (node (ref "U4") (pin "3") (pinfunction "PC14-OSC32_IN_3") (pintype "bidirectional+no_connect"))
    )
    (net (code "61") (name "unconnected-(U4B-PC15-OSC32_OUT-Pad4)") (class "Default")
      (node (ref "U4") (pin "4") (pinfunction "PC15-OSC32_OUT_4") (pintype "bidirectional+no_connect"))
    )
  )
)
